# Preamp.net
KiCad netlist of a schematic drawn in Altium Designer
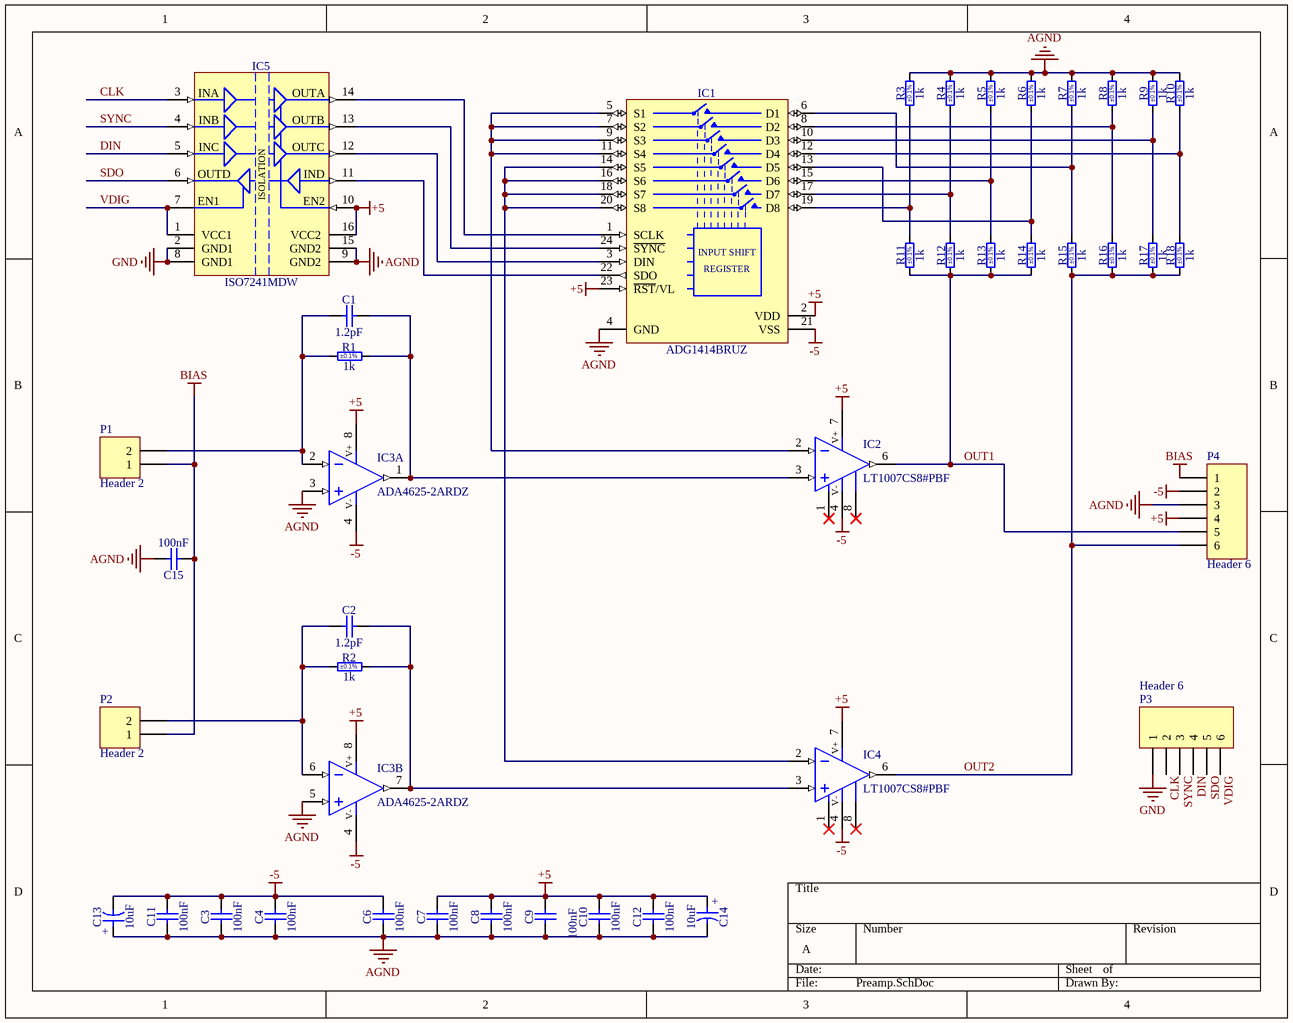
[diagram p0: Preamp.SchDoc]

(export (version "E")
  (design (tool "Eeschema 10.0.6"))
  (components
    (comp (ref "C1")
      (value "1.2pF")
      (footprint "CAPC1608X87N")
      (description "Non-polarised capacitor")
      (fields
        (field (name "PART NUMBER") "CC0603_1.2PF_50V_0.25PF_NP0")
        (field (name "VOLTAGE") "50V")
        (field (name "AUTHOR") "CERN DEM JLC")
      )
      (libsource (lib "Capacitors") (part "Capacitor - non polarized"))
    )
    (comp (ref "C2")
      (value "1.2pF")
      (footprint "CAPC1608X87N")
      (description "Non-polarised capacitor")
      (fields
        (field (name "PART NUMBER") "CC0603_1.2PF_50V_0.25PF_NP0")
        (field (name "VOLTAGE") "50V")
        (field (name "AUTHOR") "CERN DEM JLC")
      )
      (libsource (lib "Capacitors") (part "Capacitor - non polarized"))
    )
    (comp (ref "C3")
      (value "100nF")
      (footprint "CAPC2012X135N")
      (description "Non-polarised capacitor")
      (fields
        (field (name "PART NUMBER") "CC0805_100NF_50V_10%_X7R")
        (field (name "VOLTAGE") "50V")
        (field (name "AUTHOR") "CERN DEM JLC")
      )
      (libsource (lib "Capacitors") (part "Capacitor - non polarized"))
    )
    (comp (ref "C4")
      (value "100nF")
      (footprint "CAPC2012X135N")
      (description "Non-polarised capacitor")
      (fields
        (field (name "PART NUMBER") "CC0805_100NF_50V_10%_X7R")
        (field (name "VOLTAGE") "50V")
        (field (name "AUTHOR") "CERN DEM JLC")
      )
      (libsource (lib "Capacitors") (part "Capacitor - non polarized"))
    )
    (comp (ref "C6")
      (value "100nF")
      (footprint "CAPC2012X135N")
      (description "Non-polarised capacitor")
      (fields
        (field (name "PART NUMBER") "CC0805_100NF_50V_10%_X7R")
        (field (name "VOLTAGE") "50V")
        (field (name "AUTHOR") "CERN DEM JLC")
      )
      (libsource (lib "Capacitors") (part "Capacitor - non polarized"))
    )
    (comp (ref "C7")
      (value "100nF")
      (footprint "CAPC2012X135N")
      (description "Non-polarised capacitor")
      (fields
        (field (name "PART NUMBER") "CC0805_100NF_50V_10%_X7R")
        (field (name "VOLTAGE") "50V")
        (field (name "AUTHOR") "CERN DEM JLC")
      )
      (libsource (lib "Capacitors") (part "Capacitor - non polarized"))
    )
    (comp (ref "C8")
      (value "100nF")
      (footprint "CAPC2012X135N")
      (description "Non-polarised capacitor")
      (fields
        (field (name "PART NUMBER") "CC0805_100NF_50V_10%_X7R")
        (field (name "VOLTAGE") "50V")
        (field (name "AUTHOR") "CERN DEM JLC")
      )
      (libsource (lib "Capacitors") (part "Capacitor - non polarized"))
    )
    (comp (ref "C9")
      (value "100nF")
      (footprint "CAPC2012X135N")
      (description "Non-polarised capacitor")
      (fields
        (field (name "PART NUMBER") "CC0805_100NF_50V_10%_X7R")
        (field (name "VOLTAGE") "50V")
        (field (name "AUTHOR") "CERN DEM JLC")
      )
      (libsource (lib "Capacitors") (part "Capacitor - non polarized"))
    )
    (comp (ref "C10")
      (value "100nF")
      (footprint "CAPC2012X135N")
      (description "Non-polarised capacitor")
      (fields
        (field (name "PART NUMBER") "CC0805_100NF_50V_10%_X7R")
        (field (name "VOLTAGE") "50V")
        (field (name "AUTHOR") "CERN DEM JLC")
      )
      (libsource (lib "Capacitors") (part "Capacitor - non polarized"))
    )
    (comp (ref "C11")
      (value "100nF")
      (footprint "CAPC2012X135N")
      (description "Non-polarised capacitor")
      (fields
        (field (name "PART NUMBER") "CC0805_100NF_50V_10%_X7R")
        (field (name "VOLTAGE") "50V")
        (field (name "AUTHOR") "CERN DEM JLC")
      )
      (libsource (lib "Capacitors") (part "Capacitor - non polarized"))
    )
    (comp (ref "C12")
      (value "100nF")
      (footprint "CAPC2012X135N")
      (description "Non-polarised capacitor")
      (fields
        (field (name "PART NUMBER") "CC0805_100NF_50V_10%_X7R")
        (field (name "VOLTAGE") "50V")
        (field (name "AUTHOR") "CERN DEM JLC")
      )
      (libsource (lib "Capacitors") (part "Capacitor - non polarized"))
    )
    (comp (ref "C13")
      (value "10uF")
      (footprint "CAPMP7343X310N")
      (description "Polarised capacitor")
      (fields
        (field (name "PART NUMBER") "CTE7343-31_10UF_25V_10%")
        (field (name "VOLTAGE") "25V")
        (field (name "AUTHOR") "CERN DEM JMW")
      )
      (libsource (lib "Capacitors") (part "Capacitor - polarized"))
    )
    (comp (ref "C14")
      (value "10uF")
      (footprint "CAPMP7343X310N")
      (description "Polarised capacitor")
      (fields
        (field (name "PART NUMBER") "CTE7343-31_10UF_25V_10%")
        (field (name "VOLTAGE") "25V")
        (field (name "AUTHOR") "CERN DEM JMW")
      )
      (libsource (lib "Capacitors") (part "Capacitor - polarized"))
    )
    (comp (ref "C15")
      (value "100nF")
      (footprint "CAPC2012X135N")
      (description "Non-polarised capacitor")
      (fields
        (field (name "PART NUMBER") "CC0805_100NF_50V_10%_X7R")
        (field (name "VOLTAGE") "50V")
        (field (name "AUTHOR") "CERN DEM JLC")
      )
      (libsource (lib "Capacitors") (part "Capacitor - non polarized"))
    )
    (comp (ref "IC1")
      (value "ADG1414BRUZ")
      (footprint "SOP65P640X120-24N")
      (description "9.5 Ohm ON Resistance, ±15 V/+12 V/±5 V iCMOS,  Serially-Controlled Octal SPST Switches")
      (fields (field (name "MANUFACTURER") "ANALOG DEVICES") (field (name "AUTHOR") "CERN DEM MR"))
      (libsource (lib "ICs And Semiconductors") (part "ADG1414BRUZ"))
    )
    (comp (ref "IC2")
      (value "LT1007CS8#PBF")
      (footprint "SOIC127P600X175-8N")
      (description "Operational Amplifier with Offset 1-8")
      (fields (field (name "MANUFACTURER") "LINEAR TECHNOLOGY") (field (name "AUTHOR") "CERN DEM JLC"))
      (libsource (lib "ICs And Semiconductors") (part "Operational Amplifier Type3"))
    )
    (comp (ref "IC3")
      (value "ADA4625-2ARDZ")
      (footprint "SOIC127P600X175-9N-S229")
      (description "Dual Operational Amplifier")
      (fields (field (name "MANUFACTURER") "ANALOG DEVICES") (field (name "AUTHOR") "CERN DEM BC"))
      (libsource (lib "ICs And Semiconductors") (part "Operational Amplifier x2 Type1"))
    )
    (comp (ref "IC4")
      (value "LT1007CS8#PBF")
      (footprint "SOIC127P600X175-8N")
      (description "Operational Amplifier with Offset 1-8")
      (fields (field (name "MANUFACTURER") "LINEAR TECHNOLOGY") (field (name "AUTHOR") "CERN DEM JLC"))
      (libsource (lib "ICs And Semiconductors") (part "Operational Amplifier Type3"))
    )
    (comp (ref "IC5")
      (value "ISO7241MDW")
      (footprint "SOIC127P1030X265-16N")
      (description "Quad Channel, 150Mbps, Digital Isolator")
      (fields (field (name "MANUFACTURER") "TEXAS INSTRUMENTS") (field (name "AUTHOR") "CERN DEM BC"))
      (libsource (lib "ICs And Semiconductors") (part "ISO7241"))
    )
    (comp (ref "P1")
      (value "Header 2")
      (footprint "HDR1X2")
      (description "Header, 2-Pin")
      (fields (field (name "PUBLISHER") "Altium Limited"))
      (libsource (lib "Miscellaneous Connectors") (part "Header 2"))
    )
    (comp (ref "P2")
      (value "Header 2")
      (footprint "HDR1X2")
      (description "Header, 2-Pin")
      (fields (field (name "PUBLISHER") "Altium Limited"))
      (libsource (lib "Miscellaneous Connectors") (part "Header 2"))
    )
    (comp (ref "P3")
      (value "Header 6")
      (footprint "HDR1X6")
      (description "Header, 6-Pin")
      (fields (field (name "PUBLISHER") "Altium Limited"))
      (libsource (lib "") (part "Header 6_1"))
    )
    (comp (ref "P4")
      (value "Header 6")
      (footprint "HDR1X6")
      (description "Header, 6-Pin")
      (fields (field (name "PUBLISHER") "Altium Limited"))
      (libsource (lib "Miscellaneous Connectors") (part "Header 6"))
    )
    (comp (ref "R1")
      (value "1k")
      (footprint "RESC2012X60N")
      (description "Resistor - 0.1%")
      (fields
        (field (name "TOLERANCE") "±0.1%")
        (field (name "PART NUMBER") "R0805_1K_0.1%_0.1W_10PPM")
        (field (name "POWER") "0.1W")
        (field (name "AUTHOR") "CERN DEM JLC")
      )
      (libsource (lib "Resistors") (part "Resistor - 0.1%"))
    )
    (comp (ref "R2")
      (value "1k")
      (footprint "RESC2012X60N")
      (description "Resistor - 0.1%")
      (fields
        (field (name "TOLERANCE") "±0.1%")
        (field (name "PART NUMBER") "R0805_1K_0.1%_0.1W_10PPM")
        (field (name "POWER") "0.1W")
        (field (name "AUTHOR") "CERN DEM JLC")
      )
      (libsource (lib "Resistors") (part "Resistor - 0.1%"))
    )
    (comp (ref "R3")
      (value "1k")
      (footprint "RESC2012X60N")
      (description "Resistor - 0.1%")
      (fields
        (field (name "TOLERANCE") "±0.1%")
        (field (name "PART NUMBER") "R0805_1K_0.1%_0.1W_10PPM")
        (field (name "POWER") "0.1W")
        (field (name "AUTHOR") "CERN DEM JLC")
      )
      (libsource (lib "Resistors") (part "Resistor - 0.1%"))
    )
    (comp (ref "R4")
      (value "1k")
      (footprint "RESC2012X60N")
      (description "Resistor - 0.1%")
      (fields
        (field (name "TOLERANCE") "±0.1%")
        (field (name "PART NUMBER") "R0805_1K_0.1%_0.1W_10PPM")
        (field (name "POWER") "0.1W")
        (field (name "AUTHOR") "CERN DEM JLC")
      )
      (libsource (lib "Resistors") (part "Resistor - 0.1%"))
    )
    (comp (ref "R5")
      (value "1k")
      (footprint "RESC2012X60N")
      (description "Resistor - 0.1%")
      (fields
        (field (name "TOLERANCE") "±0.1%")
        (field (name "PART NUMBER") "R0805_1K_0.1%_0.1W_10PPM")
        (field (name "POWER") "0.1W")
        (field (name "AUTHOR") "CERN DEM JLC")
      )
      (libsource (lib "Resistors") (part "Resistor - 0.1%"))
    )
    (comp (ref "R6")
      (value "1k")
      (footprint "RESC2012X60N")
      (description "Resistor - 0.1%")
      (fields
        (field (name "TOLERANCE") "±0.1%")
        (field (name "PART NUMBER") "R0805_1K_0.1%_0.1W_10PPM")
        (field (name "POWER") "0.1W")
        (field (name "AUTHOR") "CERN DEM JLC")
      )
      (libsource (lib "Resistors") (part "Resistor - 0.1%"))
    )
    (comp (ref "R7")
      (value "1k")
      (footprint "RESC2012X60N")
      (description "Resistor - 0.1%")
      (fields
        (field (name "TOLERANCE") "±0.1%")
        (field (name "PART NUMBER") "R0805_1K_0.1%_0.1W_10PPM")
        (field (name "POWER") "0.1W")
        (field (name "AUTHOR") "CERN DEM JLC")
      )
      (libsource (lib "Resistors") (part "Resistor - 0.1%"))
    )
    (comp (ref "R8")
      (value "1k")
      (footprint "RESC2012X60N")
      (description "Resistor - 0.1%")
      (fields
        (field (name "TOLERANCE") "±0.1%")
        (field (name "PART NUMBER") "R0805_1K_0.1%_0.1W_10PPM")
        (field (name "POWER") "0.1W")
        (field (name "AUTHOR") "CERN DEM JLC")
      )
      (libsource (lib "Resistors") (part "Resistor - 0.1%"))
    )
    (comp (ref "R9")
      (value "1k")
      (footprint "RESC2012X60N")
      (description "Resistor - 0.1%")
      (fields
        (field (name "TOLERANCE") "±0.1%")
        (field (name "PART NUMBER") "R0805_1K_0.1%_0.1W_10PPM")
        (field (name "POWER") "0.1W")
        (field (name "AUTHOR") "CERN DEM JLC")
      )
      (libsource (lib "Resistors") (part "Resistor - 0.1%"))
    )
    (comp (ref "R10")
      (value "1k")
      (footprint "RESC2012X60N")
      (description "Resistor - 0.1%")
      (fields
        (field (name "TOLERANCE") "±0.1%")
        (field (name "PART NUMBER") "R0805_1K_0.1%_0.1W_10PPM")
        (field (name "POWER") "0.1W")
        (field (name "AUTHOR") "CERN DEM JLC")
      )
      (libsource (lib "Resistors") (part "Resistor - 0.1%"))
    )
    (comp (ref "R11")
      (value "1k")
      (footprint "RESC2012X60N")
      (description "Resistor - 0.1%")
      (fields
        (field (name "TOLERANCE") "±0.1%")
        (field (name "PART NUMBER") "R0805_1K_0.1%_0.1W_10PPM")
        (field (name "POWER") "0.1W")
        (field (name "AUTHOR") "CERN DEM JLC")
      )
      (libsource (lib "Resistors") (part "Resistor - 0.1%"))
    )
    (comp (ref "R12")
      (value "1k")
      (footprint "RESC2012X60N")
      (description "Resistor - 0.1%")
      (fields
        (field (name "TOLERANCE") "±0.1%")
        (field (name "PART NUMBER") "R0805_1K_0.1%_0.1W_10PPM")
        (field (name "POWER") "0.1W")
        (field (name "AUTHOR") "CERN DEM JLC")
      )
      (libsource (lib "Resistors") (part "Resistor - 0.1%"))
    )
    (comp (ref "R13")
      (value "1k")
      (footprint "RESC2012X60N")
      (description "Resistor - 0.1%")
      (fields
        (field (name "TOLERANCE") "±0.1%")
        (field (name "PART NUMBER") "R0805_1K_0.1%_0.1W_10PPM")
        (field (name "POWER") "0.1W")
        (field (name "AUTHOR") "CERN DEM JLC")
      )
      (libsource (lib "Resistors") (part "Resistor - 0.1%"))
    )
    (comp (ref "R14")
      (value "1k")
      (footprint "RESC2012X60N")
      (description "Resistor - 0.1%")
      (fields
        (field (name "TOLERANCE") "±0.1%")
        (field (name "PART NUMBER") "R0805_1K_0.1%_0.1W_10PPM")
        (field (name "POWER") "0.1W")
        (field (name "AUTHOR") "CERN DEM JLC")
      )
      (libsource (lib "Resistors") (part "Resistor - 0.1%"))
    )
    (comp (ref "R15")
      (value "1k")
      (footprint "RESC2012X60N")
      (description "Resistor - 0.1%")
      (fields
        (field (name "TOLERANCE") "±0.1%")
        (field (name "PART NUMBER") "R0805_1K_0.1%_0.1W_10PPM")
        (field (name "POWER") "0.1W")
        (field (name "AUTHOR") "CERN DEM JLC")
      )
      (libsource (lib "Resistors") (part "Resistor - 0.1%"))
    )
    (comp (ref "R16")
      (value "1k")
      (footprint "RESC2012X60N")
      (description "Resistor - 0.1%")
      (fields
        (field (name "TOLERANCE") "±0.1%")
        (field (name "PART NUMBER") "R0805_1K_0.1%_0.1W_10PPM")
        (field (name "POWER") "0.1W")
        (field (name "AUTHOR") "CERN DEM JLC")
      )
      (libsource (lib "Resistors") (part "Resistor - 0.1%"))
    )
    (comp (ref "R17")
      (value "1k")
      (footprint "RESC2012X60N")
      (description "Resistor - 0.1%")
      (fields
        (field (name "TOLERANCE") "±0.1%")
        (field (name "PART NUMBER") "R0805_1K_0.1%_0.1W_10PPM")
        (field (name "POWER") "0.1W")
        (field (name "AUTHOR") "CERN DEM JLC")
      )
      (libsource (lib "Resistors") (part "Resistor - 0.1%"))
    )
    (comp (ref "R18")
      (value "1k")
      (footprint "RESC2012X60N")
      (description "Resistor - 0.1%")
      (fields
        (field (name "TOLERANCE") "±0.1%")
        (field (name "PART NUMBER") "R0805_1K_0.1%_0.1W_10PPM")
        (field (name "POWER") "0.1W")
        (field (name "AUTHOR") "CERN DEM JLC")
      )
      (libsource (lib "Resistors") (part "Resistor - 0.1%"))
    )
  )
  (nets
    (net (code "1") (name "+5") (class "Default")
      (node (ref "C10") (pin "2") (pinfunction "2_2") (pintype "passive"))
      (node (ref "C12") (pin "2") (pinfunction "2_2") (pintype "passive"))
      (node (ref "C14") (pin "1") (pinfunction "1_1") (pintype "passive"))
      (node (ref "C7") (pin "2") (pinfunction "2_2") (pintype "passive"))
      (node (ref "C8") (pin "2") (pinfunction "2_2") (pintype "passive"))
      (node (ref "C9") (pin "2") (pinfunction "2_2") (pintype "passive"))
      (node (ref "IC1") (pin "2") (pinfunction "VDD_2") (pintype "power_in"))
      (node (ref "IC1") (pin "23") (pinfunction "~{RST}/VL_23") (pintype "input"))
      (node (ref "IC2") (pin "7") (pinfunction "V+_7") (pintype "power_in"))
      (node (ref "IC3") (pin "8") (pinfunction "V+_8") (pintype "power_in"))
      (node (ref "IC4") (pin "7") (pinfunction "V+_7") (pintype "power_in"))
      (node (ref "IC5") (pin "10") (pinfunction "EN2_10") (pintype "input"))
      (node (ref "IC5") (pin "16") (pinfunction "VCC2_16") (pintype "power_in"))
      (node (ref "P4") (pin "4") (pinfunction "4_4") (pintype "passive"))
    )
    (net (code "2") (name "-5") (class "Default")
      (node (ref "C11") (pin "2") (pinfunction "2_2") (pintype "passive"))
      (node (ref "C13") (pin "2") (pinfunction "2_2") (pintype "passive"))
      (node (ref "C3") (pin "2") (pinfunction "2_2") (pintype "passive"))
      (node (ref "C4") (pin "2") (pinfunction "2_2") (pintype "passive"))
      (node (ref "C6") (pin "2") (pinfunction "2_2") (pintype "passive"))
      (node (ref "IC1") (pin "21") (pinfunction "VSS_21") (pintype "power_in"))
      (node (ref "IC2") (pin "4") (pinfunction "V-_4") (pintype "power_in"))
      (node (ref "IC3") (pin "4") (pinfunction "V-_4") (pintype "power_in"))
      (node (ref "IC4") (pin "4") (pinfunction "V-_4") (pintype "power_in"))
      (node (ref "P4") (pin "2") (pinfunction "2_2") (pintype "passive"))
    )
    (net (code "3") (name "/CLK") (class "Default")
      (node (ref "IC5") (pin "3") (pinfunction "INA_3") (pintype "input"))
      (node (ref "P3") (pin "2") (pinfunction "2_2") (pintype "passive"))
    )
    (net (code "4") (name "/DIN") (class "Default")
      (node (ref "IC5") (pin "5") (pinfunction "INC_5") (pintype "input"))
      (node (ref "P3") (pin "4") (pinfunction "4_4") (pintype "passive"))
    )
    (net (code "5") (name "/OUT1") (class "Default")
      (node (ref "IC2") (pin "6") (pinfunction "OUT_6") (pintype "output"))
      (node (ref "P4") (pin "5") (pinfunction "5_5") (pintype "passive"))
      (node (ref "R11") (pin "1") (pinfunction "1_1") (pintype "passive"))
      (node (ref "R12") (pin "1") (pinfunction "1_1") (pintype "passive"))
      (node (ref "R13") (pin "1") (pinfunction "1_1") (pintype "passive"))
      (node (ref "R14") (pin "1") (pinfunction "1_1") (pintype "passive"))
    )
    (net (code "6") (name "/OUT2") (class "Default")
      (node (ref "IC4") (pin "6") (pinfunction "OUT_6") (pintype "output"))
      (node (ref "P4") (pin "6") (pinfunction "6_6") (pintype "passive"))
      (node (ref "R15") (pin "1") (pinfunction "1_1") (pintype "passive"))
      (node (ref "R16") (pin "1") (pinfunction "1_1") (pintype "passive"))
      (node (ref "R17") (pin "1") (pinfunction "1_1") (pintype "passive"))
      (node (ref "R18") (pin "1") (pinfunction "1_1") (pintype "passive"))
    )
    (net (code "7") (name "/SDO") (class "Default")
      (node (ref "IC5") (pin "6") (pinfunction "IND_6") (pintype "input"))
      (node (ref "P3") (pin "5") (pinfunction "5_5") (pintype "passive"))
    )
    (net (code "8") (name "/SYNC") (class "Default")
      (node (ref "IC5") (pin "4") (pinfunction "INB_4") (pintype "input"))
      (node (ref "P3") (pin "3") (pinfunction "3_3") (pintype "passive"))
    )
    (net (code "9") (name "/VDIG") (class "Default")
      (node (ref "IC5") (pin "1") (pinfunction "VCC1_1") (pintype "power_in"))
      (node (ref "IC5") (pin "7") (pinfunction "EN1_7") (pintype "passive"))
      (node (ref "P3") (pin "6") (pinfunction "6_6") (pintype "passive"))
    )
    (net (code "10") (name "AGND") (class "Default")
      (node (ref "C10") (pin "1") (pinfunction "1_1") (pintype "passive"))
      (node (ref "C11") (pin "1") (pinfunction "1_1") (pintype "passive"))
      (node (ref "C12") (pin "1") (pinfunction "1_1") (pintype "passive"))
      (node (ref "C13") (pin "1") (pinfunction "1_1") (pintype "passive"))
      (node (ref "C14") (pin "2") (pinfunction "2_2") (pintype "passive"))
      (node (ref "C15") (pin "2") (pinfunction "2_2") (pintype "passive"))
      (node (ref "C3") (pin "1") (pinfunction "1_1") (pintype "passive"))
      (node (ref "C4") (pin "1") (pinfunction "1_1") (pintype "passive"))
      (node (ref "C6") (pin "1") (pinfunction "1_1") (pintype "passive"))
      (node (ref "C7") (pin "1") (pinfunction "1_1") (pintype "passive"))
      (node (ref "C8") (pin "1") (pinfunction "1_1") (pintype "passive"))
      (node (ref "C9") (pin "1") (pinfunction "1_1") (pintype "passive"))
      (node (ref "IC1") (pin "4") (pinfunction "GND_4") (pintype "power_in"))
      (node (ref "IC3") (pin "3") (pinfunction "IN+_3") (pintype "input"))
      (node (ref "IC3") (pin "5") (pinfunction "IN+_5") (pintype "input"))
      (node (ref "IC5") (pin "15") (pinfunction "GND2_15") (pintype "power_in"))
      (node (ref "IC5") (pin "9") (pinfunction "GND2_9") (pintype "power_in"))
      (node (ref "P4") (pin "3") (pinfunction "3_3") (pintype "passive"))
      (node (ref "R10") (pin "2") (pinfunction "2_2") (pintype "passive"))
      (node (ref "R3") (pin "2") (pinfunction "2_2") (pintype "passive"))
      (node (ref "R4") (pin "2") (pinfunction "2_2") (pintype "passive"))
      (node (ref "R5") (pin "2") (pinfunction "2_2") (pintype "passive"))
      (node (ref "R6") (pin "2") (pinfunction "2_2") (pintype "passive"))
      (node (ref "R7") (pin "2") (pinfunction "2_2") (pintype "passive"))
      (node (ref "R8") (pin "2") (pinfunction "2_2") (pintype "passive"))
      (node (ref "R9") (pin "2") (pinfunction "2_2") (pintype "passive"))
    )
    (net (code "11") (name "BIAS") (class "Default")
      (node (ref "C15") (pin "1") (pinfunction "1_1") (pintype "passive"))
      (node (ref "P1") (pin "1") (pinfunction "1_1") (pintype "passive"))
      (node (ref "P2") (pin "1") (pinfunction "1_1") (pintype "passive"))
      (node (ref "P4") (pin "1") (pinfunction "1_1") (pintype "passive"))
    )
    (net (code "12") (name "GND") (class "Default")
      (node (ref "IC5") (pin "2") (pinfunction "GND1_2") (pintype "power_in"))
      (node (ref "IC5") (pin "8") (pinfunction "GND1_8") (pintype "power_in"))
      (node (ref "P3") (pin "1") (pinfunction "1_1") (pintype "passive"))
    )
    (net (code "13") (name "Net-(IC1-D1)") (class "Default")
      (node (ref "IC1") (pin "6") (pinfunction "D1_6") (pintype "bidirectional"))
      (node (ref "R15") (pin "2") (pinfunction "2_2") (pintype "passive"))
      (node (ref "R7") (pin "1") (pinfunction "1_1") (pintype "passive"))
    )
    (net (code "14") (name "Net-(IC1-D2)") (class "Default")
      (node (ref "IC1") (pin "8") (pinfunction "D2_8") (pintype "bidirectional"))
      (node (ref "R16") (pin "2") (pinfunction "2_2") (pintype "passive"))
      (node (ref "R8") (pin "1") (pinfunction "1_1") (pintype "passive"))
    )
    (net (code "15") (name "Net-(IC1-D3)") (class "Default")
      (node (ref "IC1") (pin "10") (pinfunction "D3_10") (pintype "bidirectional"))
      (node (ref "R17") (pin "2") (pinfunction "2_2") (pintype "passive"))
      (node (ref "R9") (pin "1") (pinfunction "1_1") (pintype "passive"))
    )
    (net (code "16") (name "Net-(IC1-D4)") (class "Default")
      (node (ref "IC1") (pin "12") (pinfunction "D4_12") (pintype "bidirectional"))
      (node (ref "R10") (pin "1") (pinfunction "1_1") (pintype "passive"))
      (node (ref "R18") (pin "2") (pinfunction "2_2") (pintype "passive"))
    )
    (net (code "17") (name "Net-(IC1-D5)") (class "Default")
      (node (ref "IC1") (pin "13") (pinfunction "D5_13") (pintype "bidirectional"))
      (node (ref "R14") (pin "2") (pinfunction "2_2") (pintype "passive"))
      (node (ref "R6") (pin "1") (pinfunction "1_1") (pintype "passive"))
    )
    (net (code "18") (name "Net-(IC1-D6)") (class "Default")
      (node (ref "IC1") (pin "15") (pinfunction "D6_15") (pintype "bidirectional"))
      (node (ref "R13") (pin "2") (pinfunction "2_2") (pintype "passive"))
      (node (ref "R5") (pin "1") (pinfunction "1_1") (pintype "passive"))
    )
    (net (code "19") (name "Net-(IC1-D7)") (class "Default")
      (node (ref "IC1") (pin "17") (pinfunction "D7_17") (pintype "bidirectional"))
      (node (ref "R12") (pin "2") (pinfunction "2_2") (pintype "passive"))
      (node (ref "R4") (pin "1") (pinfunction "1_1") (pintype "passive"))
    )
    (net (code "20") (name "Net-(IC1-D8)") (class "Default")
      (node (ref "IC1") (pin "19") (pinfunction "D8_19") (pintype "bidirectional"))
      (node (ref "R11") (pin "2") (pinfunction "2_2") (pintype "passive"))
      (node (ref "R3") (pin "1") (pinfunction "1_1") (pintype "passive"))
    )
    (net (code "21") (name "Net-(IC1-DIN)") (class "Default")
      (node (ref "IC1") (pin "3") (pinfunction "DIN_3") (pintype "input"))
      (node (ref "IC5") (pin "12") (pinfunction "OUTC_12") (pintype "output"))
    )
    (net (code "22") (name "Net-(IC1-S1)") (class "Default")
      (node (ref "IC1") (pin "11") (pinfunction "S4_11") (pintype "bidirectional"))
      (node (ref "IC1") (pin "5") (pinfunction "S1_5") (pintype "bidirectional"))
      (node (ref "IC1") (pin "7") (pinfunction "S2_7") (pintype "bidirectional"))
      (node (ref "IC1") (pin "9") (pinfunction "S3_9") (pintype "bidirectional"))
      (node (ref "IC2") (pin "2") (pinfunction "IN-_2") (pintype "input"))
    )
    (net (code "23") (name "Net-(IC1-S5)") (class "Default")
      (node (ref "IC1") (pin "14") (pinfunction "S5_14") (pintype "bidirectional"))
      (node (ref "IC1") (pin "16") (pinfunction "S6_16") (pintype "bidirectional"))
      (node (ref "IC1") (pin "18") (pinfunction "S7_18") (pintype "bidirectional"))
      (node (ref "IC1") (pin "20") (pinfunction "S8_20") (pintype "bidirectional"))
      (node (ref "IC4") (pin "2") (pinfunction "IN-_2") (pintype "input"))
    )
    (net (code "24") (name "Net-(IC1-SCLK)") (class "Default")
      (node (ref "IC1") (pin "1") (pinfunction "SCLK_1") (pintype "input"))
      (node (ref "IC5") (pin "14") (pinfunction "OUTA_14") (pintype "output"))
    )
    (net (code "25") (name "Net-(IC1-SDO)") (class "Default")
      (node (ref "IC1") (pin "22") (pinfunction "SDO_22") (pintype "output"))
      (node (ref "IC5") (pin "11") (pinfunction "OUTD_11") (pintype "output"))
    )
    (net (code "26") (name "Net-(IC1-~{SYNC})") (class "Default")
      (node (ref "IC1") (pin "24") (pinfunction "~{SYNC}_24") (pintype "input"))
      (node (ref "IC5") (pin "13") (pinfunction "OUTB_13") (pintype "output"))
    )
    (net (code "27") (name "Net-(IC2-IN+)") (class "Default")
      (node (ref "C1") (pin "2") (pinfunction "2_2") (pintype "passive"))
      (node (ref "IC2") (pin "3") (pinfunction "IN+_3") (pintype "input"))
      (node (ref "IC3") (pin "1") (pinfunction "OUT_1") (pintype "output"))
      (node (ref "R1") (pin "2") (pinfunction "2_2") (pintype "passive"))
    )
    (net (code "28") (name "Net-(IC3A-IN-)") (class "Default")
      (node (ref "C1") (pin "1") (pinfunction "1_1") (pintype "passive"))
      (node (ref "IC3") (pin "2") (pinfunction "IN-_2") (pintype "input"))
      (node (ref "P1") (pin "2") (pinfunction "2_2") (pintype "passive"))
      (node (ref "R1") (pin "1") (pinfunction "1_1") (pintype "passive"))
    )
    (net (code "29") (name "Net-(IC3B-IN-)") (class "Default")
      (node (ref "C2") (pin "1") (pinfunction "1_1") (pintype "passive"))
      (node (ref "IC3") (pin "6") (pinfunction "IN-_6") (pintype "input"))
      (node (ref "P2") (pin "2") (pinfunction "2_2") (pintype "passive"))
      (node (ref "R2") (pin "1") (pinfunction "1_1") (pintype "passive"))
    )
    (net (code "30") (name "Net-(IC3B-OUT)") (class "Default")
      (node (ref "C2") (pin "2") (pinfunction "2_2") (pintype "passive"))
      (node (ref "IC3") (pin "7") (pinfunction "OUT_7") (pintype "output"))
      (node (ref "IC4") (pin "3") (pinfunction "IN+_3") (pintype "input"))
      (node (ref "R2") (pin "2") (pinfunction "2_2") (pintype "passive"))
    )
    (net (code "31") (name "unconnected-(IC2-OFFSET-Pad1)") (class "Default")
      (node (ref "IC2") (pin "1") (pinfunction "OFFSET_1") (pintype "passive+no_connect"))
    )
    (net (code "32") (name "unconnected-(IC2-OFFSET-Pad8)") (class "Default")
      (node (ref "IC2") (pin "8") (pinfunction "OFFSET_8") (pintype "passive+no_connect"))
    )
    (net (code "33") (name "unconnected-(IC4-OFFSET-Pad1)") (class "Default")
      (node (ref "IC4") (pin "1") (pinfunction "OFFSET_1") (pintype "passive+no_connect"))
    )
    (net (code "34") (name "unconnected-(IC4-OFFSET-Pad8)") (class "Default")
      (node (ref "IC4") (pin "8") (pinfunction "OFFSET_8") (pintype "passive+no_connect"))
    )
  )
)
